# Integration_board_3008.net
KiCad netlist of a schematic drawn in EAGLE
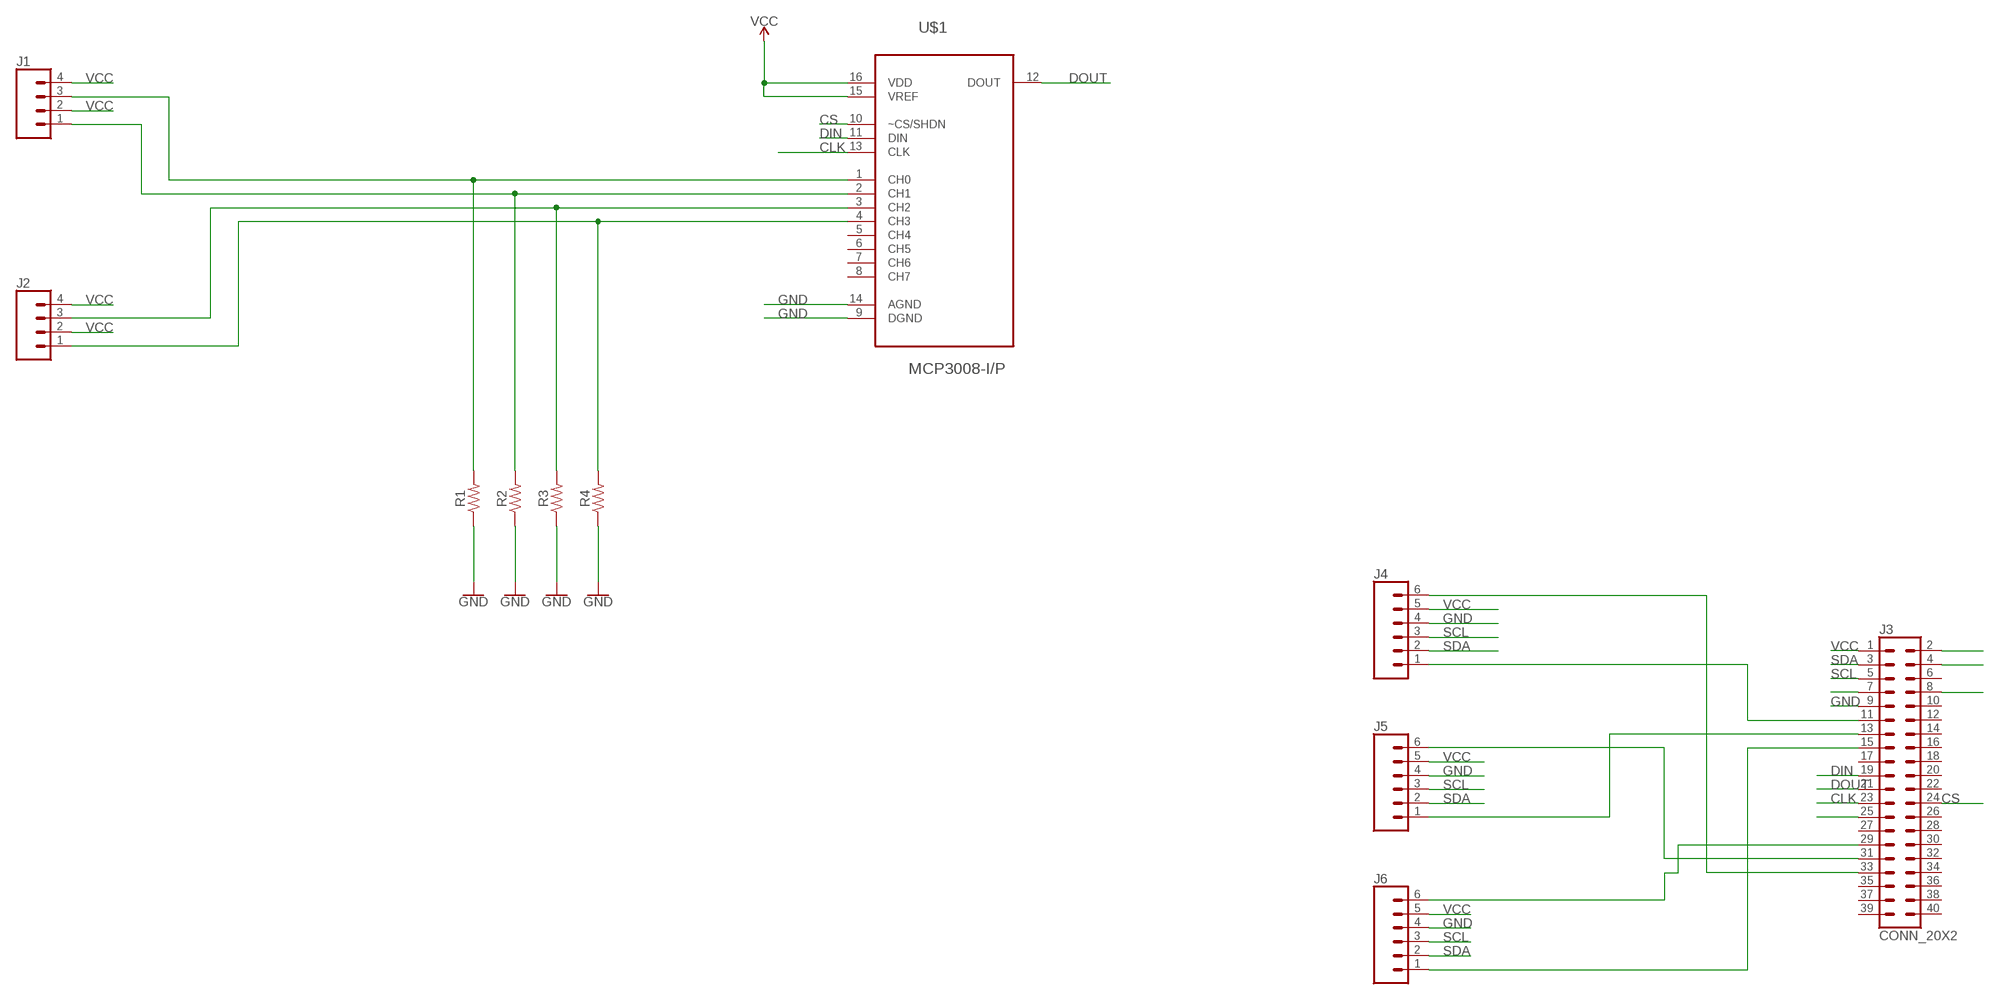
[diagram p0: schematic, sheet 1]

(export (version "E")
  (design (tool "Eeschema 10.0.6"))
  (components
    (comp (ref "J1")
      (value "CONN_04PTH")
      (footprint "eagle-import:1X04")
      (libsource (lib "eagle-import") (part "CONN_04PTH"))
    )
    (comp (ref "J2")
      (value "CONN_04PTH")
      (footprint "eagle-import:1X04")
      (libsource (lib "eagle-import") (part "CONN_04PTH"))
    )
    (comp (ref "J3")
      (value "CONN_20X2")
      (footprint "eagle-import:2X20")
      (libsource (lib "eagle-import") (part "CONN_20X2"))
    )
    (comp (ref "J4")
      (value "CONN_06SILK_FEMALE_PTH")
      (footprint "eagle-import:1X06")
      (libsource (lib "eagle-import") (part "CONN_06SILK_FEMALE_PTH"))
    )
    (comp (ref "J5")
      (value "CONN_06SILK_FEMALE_PTH")
      (footprint "eagle-import:1X06")
      (libsource (lib "eagle-import") (part "CONN_06SILK_FEMALE_PTH"))
    )
    (comp (ref "J6")
      (value "CONN_06SILK_FEMALE_PTH")
      (footprint "eagle-import:1X06")
      (libsource (lib "eagle-import") (part "CONN_06SILK_FEMALE_PTH"))
    )
    (comp (ref "R1")
      (value "RESISTORAXIAL-0.3")
      (footprint "eagle-import:AXIAL-0.3")
      (libsource (lib "eagle-import") (part "RESISTORAXIAL-0.3"))
    )
    (comp (ref "R2")
      (value "RESISTORAXIAL-0.3")
      (footprint "eagle-import:AXIAL-0.3")
      (libsource (lib "eagle-import") (part "RESISTORAXIAL-0.3"))
    )
    (comp (ref "R3")
      (value "RESISTORAXIAL-0.3")
      (footprint "eagle-import:AXIAL-0.3")
      (libsource (lib "eagle-import") (part "RESISTORAXIAL-0.3"))
    )
    (comp (ref "R4")
      (value "RESISTORAXIAL-0.3")
      (footprint "eagle-import:AXIAL-0.3")
      (libsource (lib "eagle-import") (part "RESISTORAXIAL-0.3"))
    )
    (comp (ref "U$1")
      (value "MCP3008-I/P")
      (footprint "eagle-import:DIP254P762X432-16")
      (libsource (lib "eagle-import") (part "MCP3008-I/P"))
    )
  )
  (nets
    (net (code "1") (name "/CLK") (class "Default")
      (node (ref "J3") (pin "23") (pinfunction "23_23") (pintype "passive"))
      (node (ref "U$1") (pin "13") (pinfunction "CLK_13") (pintype "input"))
    )
    (net (code "2") (name "/CS") (class "Default")
      (node (ref "J3") (pin "24") (pinfunction "24_24") (pintype "passive"))
      (node (ref "U$1") (pin "10") (pinfunction "~{CS/SHDN}_10") (pintype "input"))
    )
    (net (code "3") (name "/DIN") (class "Default")
      (node (ref "J3") (pin "19") (pinfunction "19_19") (pintype "passive"))
      (node (ref "U$1") (pin "11") (pinfunction "DIN_11") (pintype "input"))
    )
    (net (code "4") (name "/DOUT") (class "Default")
      (node (ref "J3") (pin "21") (pinfunction "21_21") (pintype "passive"))
      (node (ref "U$1") (pin "12") (pinfunction "DOUT_12") (pintype "output"))
    )
    (net (code "5") (name "/SCL") (class "Default")
      (node (ref "J3") (pin "5") (pinfunction "5_5") (pintype "passive"))
      (node (ref "J4") (pin "3") (pinfunction "3_3") (pintype "passive"))
      (node (ref "J5") (pin "3") (pinfunction "3_3") (pintype "passive"))
      (node (ref "J6") (pin "3") (pinfunction "3_3") (pintype "passive"))
    )
    (net (code "6") (name "/SDA") (class "Default")
      (node (ref "J3") (pin "3") (pinfunction "3_3") (pintype "passive"))
      (node (ref "J4") (pin "2") (pinfunction "2_2") (pintype "passive"))
      (node (ref "J5") (pin "2") (pinfunction "2_2") (pintype "passive"))
      (node (ref "J6") (pin "2") (pinfunction "2_2") (pintype "passive"))
    )
    (net (code "7") (name "GND") (class "Default")
      (node (ref "J3") (pin "9") (pinfunction "9_9") (pintype "passive"))
      (node (ref "J4") (pin "4") (pinfunction "4_4") (pintype "passive"))
      (node (ref "J5") (pin "4") (pinfunction "4_4") (pintype "passive"))
      (node (ref "J6") (pin "4") (pinfunction "4_4") (pintype "passive"))
      (node (ref "R1") (pin "P$1") (pinfunction "1_P$1") (pintype "passive"))
      (node (ref "R2") (pin "P$1") (pinfunction "1_P$1") (pintype "passive"))
      (node (ref "R3") (pin "P$1") (pinfunction "1_P$1") (pintype "passive"))
      (node (ref "R4") (pin "P$1") (pinfunction "1_P$1") (pintype "passive"))
      (node (ref "U$1") (pin "14") (pinfunction "AGND_14") (pintype "passive"))
      (node (ref "U$1") (pin "9") (pinfunction "DGND_9") (pintype "passive"))
    )
    (net (code "8") (name "Net-(J3-Pad11)") (class "Default")
      (node (ref "J3") (pin "11") (pinfunction "11_11") (pintype "passive"))
      (node (ref "J4") (pin "1") (pinfunction "1_1") (pintype "passive"))
    )
    (net (code "9") (name "Net-(J3-Pad13)") (class "Default")
      (node (ref "J3") (pin "13") (pinfunction "13_13") (pintype "passive"))
      (node (ref "J5") (pin "1") (pinfunction "1_1") (pintype "passive"))
    )
    (net (code "10") (name "Net-(J3-Pad15)") (class "Default")
      (node (ref "J3") (pin "15") (pinfunction "15_15") (pintype "passive"))
      (node (ref "J6") (pin "1") (pinfunction "1_1") (pintype "passive"))
    )
    (net (code "11") (name "Net-(J3-Pad29)") (class "Default")
      (node (ref "J3") (pin "29") (pinfunction "29_29") (pintype "passive"))
      (node (ref "J6") (pin "6") (pinfunction "6_6") (pintype "passive"))
    )
    (net (code "12") (name "Net-(J3-Pad31)") (class "Default")
      (node (ref "J3") (pin "31") (pinfunction "31_31") (pintype "passive"))
      (node (ref "J5") (pin "6") (pinfunction "6_6") (pintype "passive"))
    )
    (net (code "13") (name "Net-(J3-Pad33)") (class "Default")
      (node (ref "J3") (pin "33") (pinfunction "33_33") (pintype "passive"))
      (node (ref "J4") (pin "6") (pinfunction "6_6") (pintype "passive"))
    )
    (net (code "14") (name "Net-(R1-2)") (class "Default")
      (node (ref "J1") (pin "3") (pinfunction "3_3") (pintype "passive"))
      (node (ref "R1") (pin "P$2") (pinfunction "2_P$2") (pintype "passive"))
      (node (ref "U$1") (pin "1") (pinfunction "CH0_1") (pintype "input"))
    )
    (net (code "15") (name "Net-(R2-2)") (class "Default")
      (node (ref "J1") (pin "1") (pinfunction "1_1") (pintype "passive"))
      (node (ref "R2") (pin "P$2") (pinfunction "2_P$2") (pintype "passive"))
      (node (ref "U$1") (pin "2") (pinfunction "CH1_2") (pintype "input"))
    )
    (net (code "16") (name "Net-(R3-2)") (class "Default")
      (node (ref "J2") (pin "3") (pinfunction "3_3") (pintype "passive"))
      (node (ref "R3") (pin "P$2") (pinfunction "2_P$2") (pintype "passive"))
      (node (ref "U$1") (pin "3") (pinfunction "CH2_3") (pintype "input"))
    )
    (net (code "17") (name "Net-(R4-2)") (class "Default")
      (node (ref "J2") (pin "1") (pinfunction "1_1") (pintype "passive"))
      (node (ref "R4") (pin "P$2") (pinfunction "2_P$2") (pintype "passive"))
      (node (ref "U$1") (pin "4") (pinfunction "CH3_4") (pintype "input"))
    )
    (net (code "18") (name "VCC") (class "Default")
      (node (ref "J1") (pin "2") (pinfunction "2_2") (pintype "passive"))
      (node (ref "J1") (pin "4") (pinfunction "4_4") (pintype "passive"))
      (node (ref "J2") (pin "2") (pinfunction "2_2") (pintype "passive"))
      (node (ref "J2") (pin "4") (pinfunction "4_4") (pintype "passive"))
      (node (ref "J3") (pin "1") (pinfunction "1_1") (pintype "passive"))
      (node (ref "J4") (pin "5") (pinfunction "5_5") (pintype "passive"))
      (node (ref "J5") (pin "5") (pinfunction "5_5") (pintype "passive"))
      (node (ref "J6") (pin "5") (pinfunction "5_5") (pintype "passive"))
      (node (ref "U$1") (pin "15") (pinfunction "VREF_15") (pintype "power_in"))
      (node (ref "U$1") (pin "16") (pinfunction "VDD_16") (pintype "power_in"))
    )
    (net (code "19") (name "unconnected-(J3-Pad2)") (class "Default")
      (node (ref "J3") (pin "2") (pinfunction "2_2") (pintype "passive"))
    )
    (net (code "20") (name "unconnected-(J3-Pad4)") (class "Default")
      (node (ref "J3") (pin "4") (pinfunction "4_4") (pintype "passive"))
    )
    (net (code "21") (name "unconnected-(J3-Pad6)") (class "Default")
      (node (ref "J3") (pin "6") (pinfunction "6_6") (pintype "passive"))
    )
    (net (code "22") (name "unconnected-(J3-Pad7)") (class "Default")
      (node (ref "J3") (pin "7") (pinfunction "7_7") (pintype "passive"))
    )
    (net (code "23") (name "unconnected-(J3-Pad8)") (class "Default")
      (node (ref "J3") (pin "8") (pinfunction "8_8") (pintype "passive"))
    )
    (net (code "24") (name "unconnected-(J3-Pad10)") (class "Default")
      (node (ref "J3") (pin "10") (pinfunction "10_10") (pintype "passive"))
    )
    (net (code "25") (name "unconnected-(J3-Pad12)") (class "Default")
      (node (ref "J3") (pin "12") (pinfunction "12_12") (pintype "passive"))
    )
    (net (code "26") (name "unconnected-(J3-Pad14)") (class "Default")
      (node (ref "J3") (pin "14") (pinfunction "14_14") (pintype "passive"))
    )
    (net (code "27") (name "unconnected-(J3-Pad16)") (class "Default")
      (node (ref "J3") (pin "16") (pinfunction "16_16") (pintype "passive"))
    )
    (net (code "28") (name "unconnected-(J3-Pad17)") (class "Default")
      (node (ref "J3") (pin "17") (pinfunction "17_17") (pintype "passive"))
    )
    (net (code "29") (name "unconnected-(J3-Pad18)") (class "Default")
      (node (ref "J3") (pin "18") (pinfunction "18_18") (pintype "passive"))
    )
    (net (code "30") (name "unconnected-(J3-Pad20)") (class "Default")
      (node (ref "J3") (pin "20") (pinfunction "20_20") (pintype "passive"))
    )
    (net (code "31") (name "unconnected-(J3-Pad22)") (class "Default")
      (node (ref "J3") (pin "22") (pinfunction "22_22") (pintype "passive"))
    )
    (net (code "32") (name "unconnected-(J3-Pad25)") (class "Default")
      (node (ref "J3") (pin "25") (pinfunction "25_25") (pintype "passive"))
    )
    (net (code "33") (name "unconnected-(J3-Pad26)") (class "Default")
      (node (ref "J3") (pin "26") (pinfunction "26_26") (pintype "passive"))
    )
    (net (code "34") (name "unconnected-(J3-Pad27)") (class "Default")
      (node (ref "J3") (pin "27") (pinfunction "27_27") (pintype "passive"))
    )
    (net (code "35") (name "unconnected-(J3-Pad28)") (class "Default")
      (node (ref "J3") (pin "28") (pinfunction "28_28") (pintype "passive"))
    )
    (net (code "36") (name "unconnected-(J3-Pad30)") (class "Default")
      (node (ref "J3") (pin "30") (pinfunction "30_30") (pintype "passive"))
    )
    (net (code "37") (name "unconnected-(J3-Pad32)") (class "Default")
      (node (ref "J3") (pin "32") (pinfunction "32_32") (pintype "passive"))
    )
    (net (code "38") (name "unconnected-(J3-Pad34)") (class "Default")
      (node (ref "J3") (pin "34") (pinfunction "34_34") (pintype "passive"))
    )
    (net (code "39") (name "unconnected-(J3-Pad35)") (class "Default")
      (node (ref "J3") (pin "35") (pinfunction "35_35") (pintype "passive"))
    )
    (net (code "40") (name "unconnected-(J3-Pad36)") (class "Default")
      (node (ref "J3") (pin "36") (pinfunction "36_36") (pintype "passive"))
    )
    (net (code "41") (name "unconnected-(J3-Pad37)") (class "Default")
      (node (ref "J3") (pin "37") (pinfunction "37_37") (pintype "passive"))
    )
    (net (code "42") (name "unconnected-(J3-Pad38)") (class "Default")
      (node (ref "J3") (pin "38") (pinfunction "38_38") (pintype "passive"))
    )
    (net (code "43") (name "unconnected-(J3-Pad39)") (class "Default")
      (node (ref "J3") (pin "39") (pinfunction "39_39") (pintype "passive"))
    )
    (net (code "44") (name "unconnected-(J3-Pad40)") (class "Default")
      (node (ref "J3") (pin "40") (pinfunction "40_40") (pintype "passive"))
    )
    (net (code "45") (name "unconnected-(U$1-CH4-Pad5)") (class "Default")
      (node (ref "U$1") (pin "5") (pinfunction "CH4_5") (pintype "input"))
    )
    (net (code "46") (name "unconnected-(U$1-CH5-Pad6)") (class "Default")
      (node (ref "U$1") (pin "6") (pinfunction "CH5_6") (pintype "input"))
    )
    (net (code "47") (name "unconnected-(U$1-CH6-Pad7)") (class "Default")
      (node (ref "U$1") (pin "7") (pinfunction "CH6_7") (pintype "input"))
    )
    (net (code "48") (name "unconnected-(U$1-CH7-Pad8)") (class "Default")
      (node (ref "U$1") (pin "8") (pinfunction "CH7_8") (pintype "input"))
    )
  )
)
